# levitador.net
KiCad netlist of a schematic drawn in EAGLE
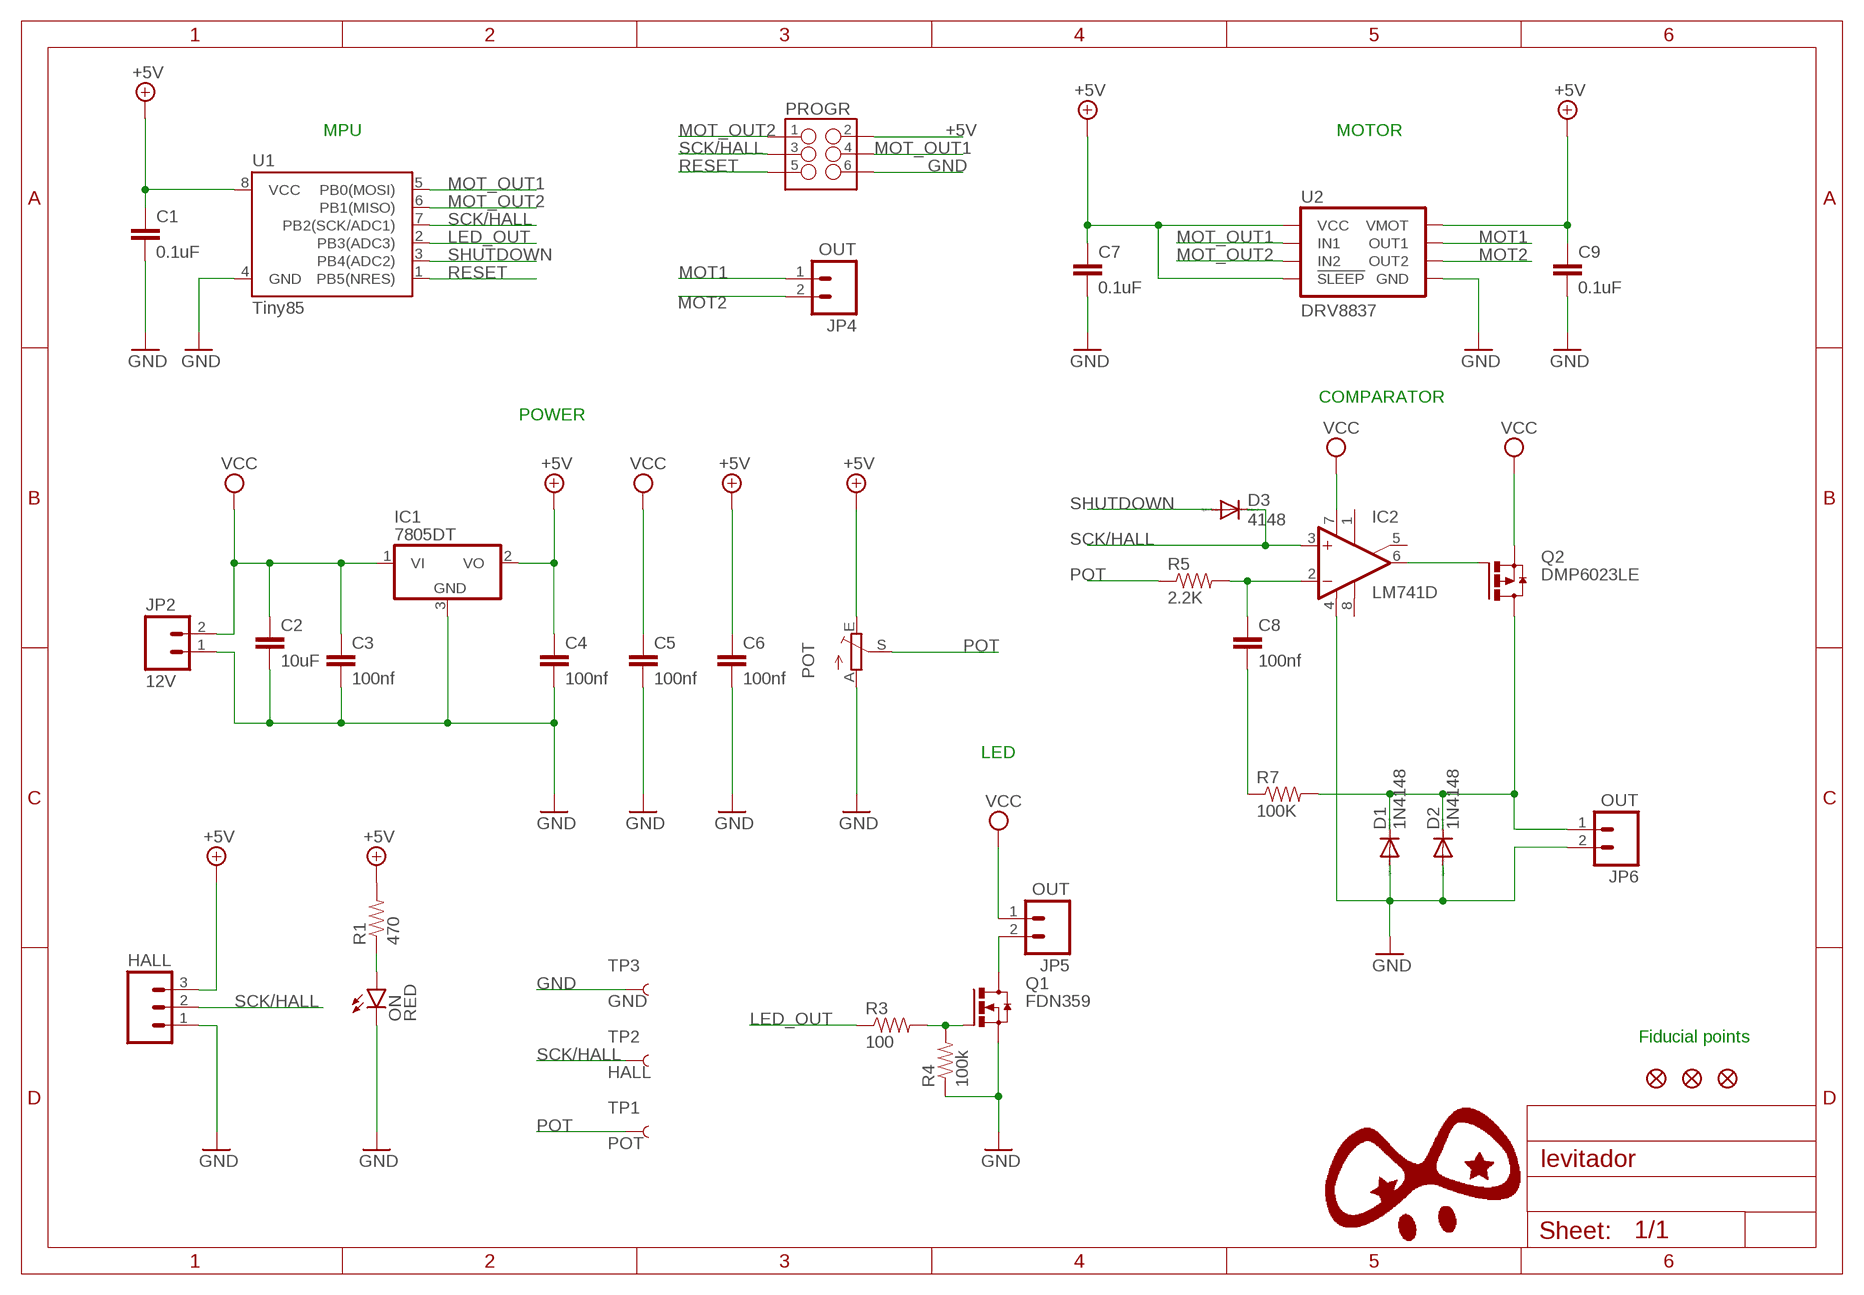
[diagram p0: schematic, sheet 1]

(export (version "E")
  (design (tool "Eeschema 10.0.6"))
  (components
    (comp (ref "C1")
      (value "0.1uF")
      (footprint "eagle-import:0402-CAP")
      (libsource (lib "eagle-import") (part "0.1UF-16V(+-10%)(0402)"))
    )
    (comp (ref "C2")
      (value "10uF")
      (footprint "eagle-import:1206")
      (libsource (lib "eagle-import") (part "CAP1206"))
    )
    (comp (ref "C3")
      (value "100nf")
      (footprint "eagle-import:C0805")
      (libsource (lib "eagle-import") (part "C-EUC0805"))
    )
    (comp (ref "C4")
      (value "100nf")
      (footprint "eagle-import:C0805")
      (libsource (lib "eagle-import") (part "C-EUC0805"))
    )
    (comp (ref "C5")
      (value "100nf")
      (footprint "eagle-import:C0805")
      (libsource (lib "eagle-import") (part "C-EUC0805"))
    )
    (comp (ref "C6")
      (value "100nf")
      (footprint "eagle-import:C0805")
      (libsource (lib "eagle-import") (part "C-EUC0805"))
    )
    (comp (ref "C7")
      (value "0.1uF")
      (footprint "eagle-import:0402-CAP")
      (libsource (lib "eagle-import") (part "0.1UF-16V(+-10%)(0402)"))
    )
    (comp (ref "C8")
      (value "100nf")
      (footprint "eagle-import:C0805")
      (libsource (lib "eagle-import") (part "C-EUC0805"))
    )
    (comp (ref "C9")
      (value "0.1uF")
      (footprint "eagle-import:0402-CAP")
      (libsource (lib "eagle-import") (part "0.1UF-16V(+-10%)(0402)"))
    )
    (comp (ref "D1")
      (value "1N4148")
      (footprint "eagle-import:MINIMELF")
      (libsource (lib "eagle-import") (part "DIODE-MINIMELF"))
    )
    (comp (ref "D2")
      (value "1N4148")
      (footprint "eagle-import:MINIMELF")
      (libsource (lib "eagle-import") (part "DIODE-MINIMELF"))
    )
    (comp (ref "D3")
      (value "4148")
      (footprint "eagle-import:MICROMELF-W")
      (libsource (lib "eagle-import") (part "DIODE-MICROMELF-W"))
    )
    (comp (ref "FID1")
      (value "FIDUCIAL1X2")
      (footprint "eagle-import:FIDUCIAL-1X2")
      (libsource (lib "eagle-import") (part "FIDUCIAL1X2"))
    )
    (comp (ref "FID2")
      (value "FIDUCIAL1X2")
      (footprint "eagle-import:FIDUCIAL-1X2")
      (libsource (lib "eagle-import") (part "FIDUCIAL1X2"))
    )
    (comp (ref "FID3")
      (value "FIDUCIAL1X2")
      (footprint "eagle-import:FIDUCIAL-1X2")
      (libsource (lib "eagle-import") (part "FIDUCIAL1X2"))
    )
    (comp (ref "HALL")
      (value "M03LOCK")
      (footprint "eagle-import:1X03_LOCK")
      (libsource (lib "eagle-import") (part "M03LOCK"))
    )
    (comp (ref "IC1")
      (value "7805DT")
      (footprint "eagle-import:TO252")
      (libsource (lib "eagle-import") (part "78DT05"))
    )
    (comp (ref "IC2")
      (value "LM741D")
      (footprint "eagle-import:SO08")
      (libsource (lib "eagle-import") (part "741DLM"))
    )
    (comp (ref "JP2")
      (value "12V")
      (footprint "eagle-import:MOLEX-1X2")
      (libsource (lib "eagle-import") (part "M02POLAR"))
    )
    (comp (ref "JP4")
      (value "OUT")
      (footprint "eagle-import:MOLEX-1X2")
      (libsource (lib "eagle-import") (part "M02POLAR"))
    )
    (comp (ref "JP5")
      (value "OUT")
      (footprint "eagle-import:MOLEX-1X2")
      (libsource (lib "eagle-import") (part "M02POLAR"))
    )
    (comp (ref "JP6")
      (value "OUT")
      (footprint "eagle-import:MOLEX-1X2")
      (libsource (lib "eagle-import") (part "M02POLAR"))
    )
    (comp (ref "ON")
      (value "RED")
      (footprint "eagle-import:LED-0603")
      (libsource (lib "eagle-import") (part "LED-RED0603"))
    )
    (comp (ref "POT")
      (value "TRIM_EU-B64W")
      (footprint "eagle-import:B64W")
      (libsource (lib "eagle-import") (part "TRIM_EU-B64W"))
    )
    (comp (ref "PROGR")
      (value "M03X2")
      (footprint "eagle-import:2X3_SMD")
      (libsource (lib "eagle-import") (part "M03X2"))
    )
    (comp (ref "Q1")
      (value "FDN359")
      (footprint "eagle-import:SUPER-SOT3")
      (libsource (lib "eagle-import") (part "FDN359"))
    )
    (comp (ref "Q2")
      (value "DMP6023LE")
      (footprint "eagle-import:SOT223")
      (libsource (lib "eagle-import") (part "DMP6023LE"))
    )
    (comp (ref "R1")
      (value "470")
      (footprint "eagle-import:0805")
      (libsource (lib "eagle-import") (part "RESISTOR0805-RES"))
    )
    (comp (ref "R3")
      (value "100")
      (footprint "eagle-import:0805")
      (libsource (lib "eagle-import") (part "RESISTOR0805-RES"))
    )
    (comp (ref "R4")
      (value "100k")
      (footprint "eagle-import:0805")
      (libsource (lib "eagle-import") (part "RESISTOR0805-RES"))
    )
    (comp (ref "R5")
      (value "2.2K")
      (footprint "eagle-import:0805")
      (libsource (lib "eagle-import") (part "RESISTOR0805-RES"))
    )
    (comp (ref "R7")
      (value "100K")
      (footprint "eagle-import:0805")
      (libsource (lib "eagle-import") (part "RESISTOR0805-RES"))
    )
    (comp (ref "TP1")
      (value "POT")
      (footprint "eagle-import:TP_15TH")
      (libsource (lib "eagle-import") (part "TEST-POINTTP_15TH_THRU"))
    )
    (comp (ref "TP2")
      (value "HALL")
      (footprint "eagle-import:TP_15TH")
      (libsource (lib "eagle-import") (part "TEST-POINTTP_15TH_THRU"))
    )
    (comp (ref "TP3")
      (value "GND")
      (footprint "eagle-import:TP_15TH")
      (libsource (lib "eagle-import") (part "TEST-POINTTP_15TH_THRU"))
    )
    (comp (ref "U1")
      (value "Tiny85")
      (footprint "eagle-import:SO08-EIAJ")
      (libsource (lib "eagle-import") (part "ATTINY45TINY45-20-SMT"))
    )
    (comp (ref "U2")
      (value "DRV8837")
      (footprint "eagle-import:DSG")
      (libsource (lib "eagle-import") (part "DRV8837"))
    )
  )
  (nets
    (net (code "1") (name "+5V") (class "Default")
      (node (ref "C1") (pin "1") (pinfunction "1_1") (pintype "passive"))
      (node (ref "C4") (pin "1") (pinfunction "1_1") (pintype "passive"))
      (node (ref "C6") (pin "1") (pinfunction "1_1") (pintype "passive"))
      (node (ref "C7") (pin "1") (pinfunction "1_1") (pintype "passive"))
      (node (ref "C9") (pin "1") (pinfunction "1_1") (pintype "passive"))
      (node (ref "HALL") (pin "3") (pinfunction "3_3") (pintype "passive"))
      (node (ref "IC1") (pin "2") (pinfunction "VO_2") (pintype "passive"))
      (node (ref "POT") (pin "E") (pinfunction "E_E") (pintype "passive"))
      (node (ref "PROGR") (pin "2") (pinfunction "2_2") (pintype "bidirectional"))
      (node (ref "R1") (pin "2") (pinfunction "2_2") (pintype "passive"))
      (node (ref "U1") (pin "8") (pinfunction "VCC_8") (pintype "bidirectional"))
      (node (ref "U2") (pin "1") (pinfunction "VMOT_1") (pintype "bidirectional"))
      (node (ref "U2") (pin "7") (pinfunction "~{SLEEP}_7") (pintype "bidirectional"))
      (node (ref "U2") (pin "8") (pinfunction "VCC_8") (pintype "bidirectional"))
    )
    (net (code "2") (name "/LED_OUT") (class "Default")
      (node (ref "R3") (pin "1") (pinfunction "1_1") (pintype "passive"))
      (node (ref "U1") (pin "2") (pinfunction "PB3(ADC3)_2") (pintype "bidirectional"))
    )
    (net (code "3") (name "/MOT1") (class "Default")
      (node (ref "JP4") (pin "1") (pinfunction "1_1") (pintype "passive"))
      (node (ref "U2") (pin "2") (pinfunction "OUT1_2") (pintype "bidirectional"))
    )
    (net (code "4") (name "/MOT2") (class "Default")
      (node (ref "JP4") (pin "2") (pinfunction "2_2") (pintype "passive"))
      (node (ref "U2") (pin "3") (pinfunction "OUT2_3") (pintype "bidirectional"))
    )
    (net (code "5") (name "/MOT_OUT1") (class "Default")
      (node (ref "PROGR") (pin "4") (pinfunction "4_4") (pintype "bidirectional"))
      (node (ref "U1") (pin "5") (pinfunction "PB0(MOSI)_5") (pintype "bidirectional"))
      (node (ref "U2") (pin "6") (pinfunction "IN1_6") (pintype "bidirectional"))
    )
    (net (code "6") (name "/MOT_OUT2") (class "Default")
      (node (ref "PROGR") (pin "1") (pinfunction "1_1") (pintype "bidirectional"))
      (node (ref "U1") (pin "6") (pinfunction "PB1(MISO)_6") (pintype "bidirectional"))
      (node (ref "U2") (pin "5") (pinfunction "IN2_5") (pintype "bidirectional"))
    )
    (net (code "7") (name "/POT") (class "Default")
      (node (ref "POT") (pin "S") (pinfunction "S_S") (pintype "passive"))
      (node (ref "R5") (pin "1") (pinfunction "1_1") (pintype "passive"))
      (node (ref "TP1") (pin "P$1") (pinfunction "1_P$1") (pintype "bidirectional"))
    )
    (net (code "8") (name "/RESET") (class "Default")
      (node (ref "PROGR") (pin "5") (pinfunction "5_5") (pintype "bidirectional"))
      (node (ref "U1") (pin "1") (pinfunction "PB5(NRES)_1") (pintype "bidirectional"))
    )
    (net (code "9") (name "/SCK{slash}HALL") (class "Default")
      (node (ref "D3") (pin "C") (pinfunction "C_C") (pintype "passive"))
      (node (ref "HALL") (pin "2") (pinfunction "2_2") (pintype "passive"))
      (node (ref "IC2") (pin "3") (pinfunction "+IN_3") (pintype "input"))
      (node (ref "PROGR") (pin "3") (pinfunction "3_3") (pintype "bidirectional"))
      (node (ref "TP2") (pin "P$1") (pinfunction "1_P$1") (pintype "bidirectional"))
      (node (ref "U1") (pin "7") (pinfunction "PB2(SCK/ADC1)_7") (pintype "bidirectional"))
    )
    (net (code "10") (name "/SHUTDOWN") (class "Default")
      (node (ref "D3") (pin "A") (pinfunction "A_A") (pintype "passive"))
      (node (ref "U1") (pin "3") (pinfunction "PB4(ADC2)_3") (pintype "bidirectional"))
    )
    (net (code "11") (name "GND") (class "Default")
      (node (ref "C1") (pin "2") (pinfunction "2_2") (pintype "passive"))
      (node (ref "C2") (pin "2") (pinfunction "2_2") (pintype "passive"))
      (node (ref "C3") (pin "2") (pinfunction "2_2") (pintype "passive"))
      (node (ref "C4") (pin "2") (pinfunction "2_2") (pintype "passive"))
      (node (ref "C5") (pin "2") (pinfunction "2_2") (pintype "passive"))
      (node (ref "C6") (pin "2") (pinfunction "2_2") (pintype "passive"))
      (node (ref "C7") (pin "2") (pinfunction "2_2") (pintype "passive"))
      (node (ref "C9") (pin "2") (pinfunction "2_2") (pintype "passive"))
      (node (ref "D1") (pin "A") (pinfunction "A_A") (pintype "passive"))
      (node (ref "D2") (pin "A") (pinfunction "A_A") (pintype "passive"))
      (node (ref "HALL") (pin "1") (pinfunction "1_1") (pintype "passive"))
      (node (ref "IC1") (pin "3") (pinfunction "GND_3") (pintype "passive"))
      (node (ref "IC2") (pin "4") (pinfunction "V-_4") (pintype "power_in"))
      (node (ref "JP2") (pin "1") (pinfunction "1_1") (pintype "passive"))
      (node (ref "JP6") (pin "2") (pinfunction "2_2") (pintype "passive"))
      (node (ref "ON") (pin "C") (pinfunction "C_C") (pintype "passive"))
      (node (ref "POT") (pin "A") (pinfunction "A_A") (pintype "passive"))
      (node (ref "PROGR") (pin "6") (pinfunction "6_6") (pintype "bidirectional"))
      (node (ref "Q1") (pin "2") (pinfunction "S_2") (pintype "passive"))
      (node (ref "R4") (pin "1") (pinfunction "1_1") (pintype "passive"))
      (node (ref "TP3") (pin "P$1") (pinfunction "1_P$1") (pintype "bidirectional"))
      (node (ref "U1") (pin "4") (pinfunction "GND_4") (pintype "bidirectional"))
      (node (ref "U2") (pin "4") (pinfunction "GND_4") (pintype "bidirectional"))
      (node (ref "U2") (pin "PAD") (pinfunction "GND_PAD") (pintype "bidirectional"))
    )
    (net (code "12") (name "Net-(C8-Pad2)") (class "Default")
      (node (ref "C8") (pin "2") (pinfunction "2_2") (pintype "passive"))
      (node (ref "R7") (pin "1") (pinfunction "1_1") (pintype "passive"))
    )
    (net (code "13") (name "Net-(D1-PadC)") (class "Default")
      (node (ref "D1") (pin "C") (pinfunction "C_C") (pintype "passive"))
      (node (ref "D2") (pin "C") (pinfunction "C_C") (pintype "passive"))
      (node (ref "JP6") (pin "1") (pinfunction "1_1") (pintype "passive"))
      (node (ref "Q2") (pin "2") (pinfunction "D_2") (pintype "passive"))
      (node (ref "Q2") (pin "4") (pinfunction "D_4") (pintype "passive"))
      (node (ref "R7") (pin "2") (pinfunction "2_2") (pintype "passive"))
    )
    (net (code "14") (name "Net-(IC2--IN)") (class "Default")
      (node (ref "C8") (pin "1") (pinfunction "1_1") (pintype "passive"))
      (node (ref "IC2") (pin "2") (pinfunction "-IN_2") (pintype "input"))
      (node (ref "R5") (pin "2") (pinfunction "2_2") (pintype "passive"))
    )
    (net (code "15") (name "Net-(IC2-OUT)") (class "Default")
      (node (ref "IC2") (pin "6") (pinfunction "OUT_6") (pintype "output"))
      (node (ref "Q2") (pin "1") (pinfunction "G_1") (pintype "passive"))
    )
    (net (code "16") (name "Net-(ON-PadA)") (class "Default")
      (node (ref "ON") (pin "A") (pinfunction "A_A") (pintype "passive"))
      (node (ref "R1") (pin "1") (pinfunction "1_1") (pintype "passive"))
    )
    (net (code "17") (name "Net-(Q1-D)") (class "Default")
      (node (ref "JP5") (pin "2") (pinfunction "2_2") (pintype "passive"))
      (node (ref "Q1") (pin "3") (pinfunction "D_3") (pintype "passive"))
    )
    (net (code "18") (name "Net-(Q1-G)") (class "Default")
      (node (ref "Q1") (pin "1") (pinfunction "G_1") (pintype "passive"))
      (node (ref "R3") (pin "2") (pinfunction "2_2") (pintype "passive"))
      (node (ref "R4") (pin "2") (pinfunction "2_2") (pintype "passive"))
    )
    (net (code "19") (name "VCC") (class "Default")
      (node (ref "C2") (pin "1") (pinfunction "1_1") (pintype "passive"))
      (node (ref "C3") (pin "1") (pinfunction "1_1") (pintype "passive"))
      (node (ref "C5") (pin "1") (pinfunction "1_1") (pintype "passive"))
      (node (ref "IC1") (pin "1") (pinfunction "VI_1") (pintype "input"))
      (node (ref "IC2") (pin "7") (pinfunction "V+_7") (pintype "power_in"))
      (node (ref "JP2") (pin "2") (pinfunction "2_2") (pintype "passive"))
      (node (ref "JP5") (pin "1") (pinfunction "1_1") (pintype "passive"))
      (node (ref "Q2") (pin "3") (pinfunction "S_3") (pintype "passive"))
    )
    (net (code "20") (name "unconnected-(IC2-ON1-Pad1)") (class "Default")
      (node (ref "IC2") (pin "1") (pinfunction "ON1_1") (pintype "passive"))
    )
    (net (code "21") (name "unconnected-(IC2-ON2-Pad5)") (class "Default")
      (node (ref "IC2") (pin "5") (pinfunction "ON2_5") (pintype "passive"))
    )
    (net (code "22") (name "unconnected-(IC2-OPT-Pad8)") (class "Default")
      (node (ref "IC2") (pin "8") (pinfunction "OPT_8") (pintype "passive"))
    )
  )
)
